# mcu_peripheral.net
KiCad netlist of a schematic drawn in Altium Designer
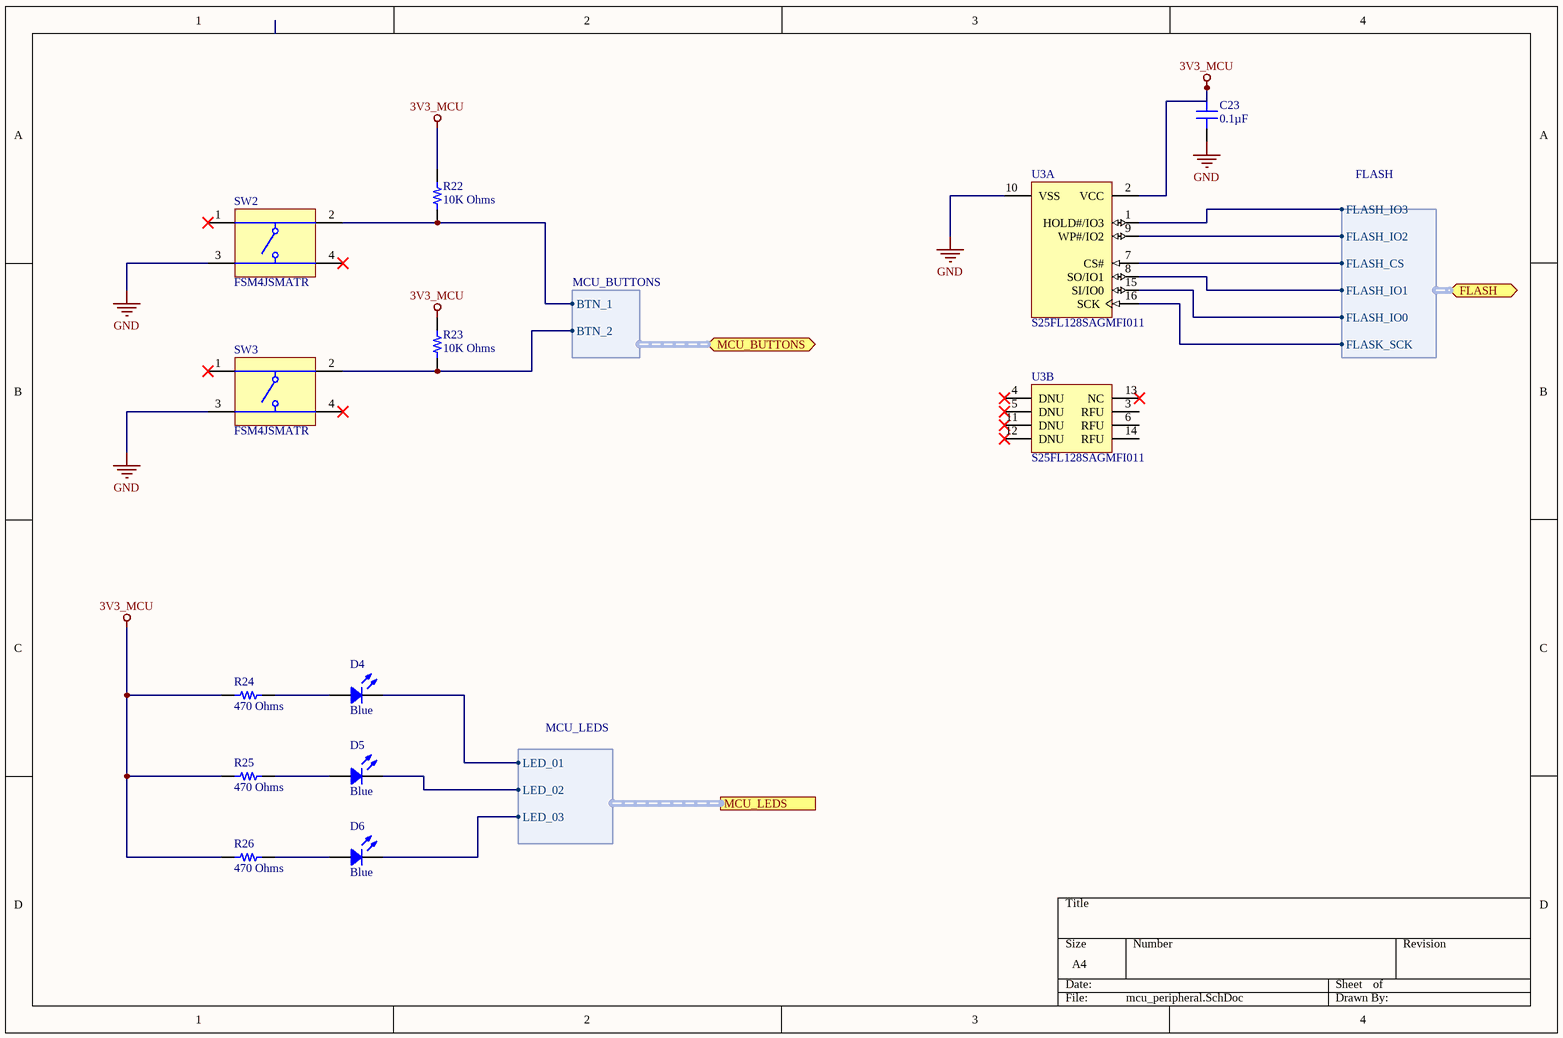
[diagram p0: mcu_peripheral.SchDoc]

(export (version "E")
  (design (tool "Eeschema 10.0.6"))
  (components
    (comp (ref "C23")
      (value "0.1µF")
      (footprint "CAP 0603_1608")
      (description "CAP CER 0.1UF 50V X7R 0603")
      (fields (field (name "PART NUMBER") "C0603C104K5RAC7411") (field (name "MANUFACTURER") "KEMET"))
      (libsource (lib "Celestial Altium Library - altium_library (2)") (part "Capacitor"))
    )
    (comp (ref "D4")
      (value "Blue")
      (footprint "LED 0603_1608 BLUE")
      (description "LED BLUE 0603 SMD")
      (fields
        (field (name "PART NUMBER") "VLMB1300-GS08")
        (field (name "MANUFACTURER") "Vishay Semiconductor Opto Division")
      )
      (libsource (lib "Celestial Altium Library - altium_library (2)") (part "LED"))
    )
    (comp (ref "D5")
      (value "Blue")
      (footprint "LED 0603_1608 BLUE")
      (description "LED BLUE 0603 SMD")
      (fields
        (field (name "PART NUMBER") "VLMB1300-GS08")
        (field (name "MANUFACTURER") "Vishay Semiconductor Opto Division")
      )
      (libsource (lib "Celestial Altium Library - altium_library (2)") (part "LED"))
    )
    (comp (ref "D6")
      (value "Blue")
      (footprint "LED 0603_1608 BLUE")
      (description "LED BLUE 0603 SMD")
      (fields
        (field (name "PART NUMBER") "VLMB1300-GS08")
        (field (name "MANUFACTURER") "Vishay Semiconductor Opto Division")
      )
      (libsource (lib "Celestial Altium Library - altium_library (2)") (part "LED"))
    )
    (comp (ref "R22")
      (value "10K Ohms")
      (footprint "RES 0603_1608")
      (description "RES SMD 470 OHM 5% 1/4W 0603")
      (fields (field (name "PART NUMBER") "CRCW0603470RJNEAHP") (field (name "MANUFACTURER") "Vishay Dale"))
      (libsource (lib "Celestial Altium Library - altium_library (2)") (part "Resistor"))
    )
    (comp (ref "R23")
      (value "10K Ohms")
      (footprint "RES 0603_1608")
      (description "RES SMD 470 OHM 5% 1/4W 0603")
      (fields (field (name "PART NUMBER") "CRCW0603470RJNEAHP") (field (name "MANUFACTURER") "Vishay Dale"))
      (libsource (lib "Celestial Altium Library - altium_library (2)") (part "Resistor"))
    )
    (comp (ref "R24")
      (value "470 Ohms")
      (footprint "RES 0603_1608")
      (description "RES SMD 470 OHM 5% 1/4W 0603")
      (fields (field (name "PART NUMBER") "CRCW0603470RJNEAHP") (field (name "MANUFACTURER") "Vishay Dale"))
      (libsource (lib "Celestial Altium Library - altium_library (2)") (part "Resistor"))
    )
    (comp (ref "R25")
      (value "470 Ohms")
      (footprint "RES 0603_1608")
      (description "RES SMD 470 OHM 5% 1/4W 0603")
      (fields (field (name "PART NUMBER") "CRCW0603470RJNEAHP") (field (name "MANUFACTURER") "Vishay Dale"))
      (libsource (lib "Celestial Altium Library - altium_library (2)") (part "Resistor"))
    )
    (comp (ref "R26")
      (value "470 Ohms")
      (footprint "RES 0603_1608")
      (description "RES SMD 470 OHM 5% 1/4W 0603")
      (fields (field (name "PART NUMBER") "CRCW0603470RJNEAHP") (field (name "MANUFACTURER") "Vishay Dale"))
      (libsource (lib "Celestial Altium Library - altium_library (2)") (part "Resistor"))
    )
    (comp (ref "SW2")
      (value "FSM4JSMATR")
      (footprint "TECO-FSM4JSMATR_V")
      (description "Micro Miniature Push Button Switch FSM JSM, 50 mA, -35 to 85 degC, 4-Pin SMD, RoHS, Tape and Reel")
      (fields (field (name "MANUFACTURER") "TE Connectivity"))
      (libsource (lib "Altium Content Vault") (part "SW-SPST-4_A"))
    )
    (comp (ref "SW3")
      (value "FSM4JSMATR")
      (footprint "TECO-FSM4JSMATR_V")
      (description "Micro Miniature Push Button Switch FSM JSM, 50 mA, -35 to 85 degC, 4-Pin SMD, RoHS, Tape and Reel")
      (fields (field (name "MANUFACTURER") "TE Connectivity"))
      (libsource (lib "Altium Content Vault") (part "SW-SPST-4_A"))
    )
    (comp (ref "U3")
      (value "S25FL128SAGMFI011")
      (footprint "SPSN-SOIC-16_L")
      (fields (field (name "MANUFACTURER") "Spansion"))
      (libsource (lib "") (part "SPSN-S25FL128S-16_1"))
    )
  )
  (nets
    (net (code "4") (name "/BTN_1") (class "Default")
      (node (ref "R22") (pin "1") (pinfunction "1_1") (pintype "passive"))
      (node (ref "SW2") (pin "2") (pinfunction "2_2") (pintype "passive"))
    )
    (net (code "5") (name "/BTN_2") (class "Default")
      (node (ref "R23") (pin "1") (pinfunction "1_1") (pintype "passive"))
      (node (ref "SW3") (pin "2") (pinfunction "2_2") (pintype "passive"))
    )
    (net (code "6") (name "/FLASH_CS") (class "Default")
      (node (ref "U3") (pin "7") (pinfunction "CS#_7") (pintype "input"))
    )
    (net (code "7") (name "/FLASH_IO0") (class "Default")
      (node (ref "U3") (pin "15") (pinfunction "SI/IO0_15") (pintype "bidirectional"))
    )
    (net (code "8") (name "/FLASH_IO1") (class "Default")
      (node (ref "U3") (pin "8") (pinfunction "SO/IO1_8") (pintype "bidirectional"))
    )
    (net (code "9") (name "/FLASH_IO2") (class "Default")
      (node (ref "U3") (pin "9") (pinfunction "WP#/IO2_9") (pintype "bidirectional"))
    )
    (net (code "10") (name "/FLASH_IO3") (class "Default")
      (node (ref "U3") (pin "1") (pinfunction "HOLD#/IO3_1") (pintype "bidirectional"))
    )
    (net (code "11") (name "/FLASK_SCK") (class "Default")
      (node (ref "U3") (pin "16") (pinfunction "SCK_16") (pintype "input"))
    )
    (net (code "12") (name "/LED_01") (class "Default")
      (node (ref "D4") (pin "2") (pinfunction "2_2") (pintype "passive"))
    )
    (net (code "13") (name "/LED_02") (class "Default")
      (node (ref "D5") (pin "2") (pinfunction "2_2") (pintype "passive"))
    )
    (net (code "14") (name "/LED_03") (class "Default")
      (node (ref "D6") (pin "2") (pinfunction "2_2") (pintype "passive"))
    )
    (net (code "18") (name "3V3_MCU") (class "Default")
      (node (ref "C23") (pin "2") (pinfunction "2_2") (pintype "passive"))
      (node (ref "R22") (pin "2") (pinfunction "2_2") (pintype "passive"))
      (node (ref "R23") (pin "2") (pinfunction "2_2") (pintype "passive"))
      (node (ref "R24") (pin "1") (pinfunction "1_1") (pintype "passive"))
      (node (ref "R25") (pin "1") (pinfunction "1_1") (pintype "passive"))
      (node (ref "R26") (pin "1") (pinfunction "1_1") (pintype "passive"))
      (node (ref "U3") (pin "2") (pinfunction "VCC_2") (pintype "power_in"))
    )
    (net (code "19") (name "GND") (class "Default")
      (node (ref "C23") (pin "1") (pinfunction "1_1") (pintype "passive"))
      (node (ref "SW2") (pin "3") (pinfunction "3_3") (pintype "passive"))
      (node (ref "SW3") (pin "3") (pinfunction "3_3") (pintype "passive"))
      (node (ref "U3") (pin "10") (pinfunction "VSS_10") (pintype "power_in"))
    )
    (net (code "20") (name "Net-(D4-Pad1)") (class "Default")
      (node (ref "D4") (pin "1") (pinfunction "1_1") (pintype "passive"))
      (node (ref "R24") (pin "2") (pinfunction "2_2") (pintype "passive"))
    )
    (net (code "21") (name "Net-(D5-Pad1)") (class "Default")
      (node (ref "D5") (pin "1") (pinfunction "1_1") (pintype "passive"))
      (node (ref "R25") (pin "2") (pinfunction "2_2") (pintype "passive"))
    )
    (net (code "22") (name "Net-(D6-Pad1)") (class "Default")
      (node (ref "D6") (pin "1") (pinfunction "1_1") (pintype "passive"))
      (node (ref "R26") (pin "2") (pinfunction "2_2") (pintype "passive"))
    )
    (net (code "23") (name "unconnected-(SW2-Pad1)") (class "Default")
      (node (ref "SW2") (pin "1") (pinfunction "1_1") (pintype "passive+no_connect"))
    )
    (net (code "24") (name "unconnected-(SW2-Pad4)") (class "Default")
      (node (ref "SW2") (pin "4") (pinfunction "4_4") (pintype "passive+no_connect"))
    )
    (net (code "25") (name "unconnected-(SW3-Pad1)") (class "Default")
      (node (ref "SW3") (pin "1") (pinfunction "1_1") (pintype "passive+no_connect"))
    )
    (net (code "26") (name "unconnected-(SW3-Pad4)") (class "Default")
      (node (ref "SW3") (pin "4") (pinfunction "4_4") (pintype "passive+no_connect"))
    )
    (net (code "27") (name "unconnected-(U3B-DNU-Pad4)") (class "Default")
      (node (ref "U3") (pin "4") (pinfunction "DNU_4") (pintype "passive+no_connect"))
    )
    (net (code "28") (name "unconnected-(U3B-DNU-Pad5)") (class "Default")
      (node (ref "U3") (pin "5") (pinfunction "DNU_5") (pintype "passive+no_connect"))
    )
    (net (code "29") (name "unconnected-(U3B-DNU-Pad11)") (class "Default")
      (node (ref "U3") (pin "11") (pinfunction "DNU_11") (pintype "passive+no_connect"))
    )
    (net (code "30") (name "unconnected-(U3B-DNU-Pad12)") (class "Default")
      (node (ref "U3") (pin "12") (pinfunction "DNU_12") (pintype "passive+no_connect"))
    )
    (net (code "31") (name "unconnected-(U3B-NC-Pad13)") (class "Default")
      (node (ref "U3") (pin "13") (pinfunction "NC_13") (pintype "passive+no_connect"))
    )
    (net (code "32") (name "unconnected-(U3B-RFU-Pad3)") (class "Default")
      (node (ref "U3") (pin "3") (pinfunction "RFU_3") (pintype "passive"))
    )
    (net (code "33") (name "unconnected-(U3B-RFU-Pad6)") (class "Default")
      (node (ref "U3") (pin "6") (pinfunction "RFU_6") (pintype "passive"))
    )
    (net (code "34") (name "unconnected-(U3B-RFU-Pad14)") (class "Default")
      (node (ref "U3") (pin "14") (pinfunction "RFU_14") (pintype "passive"))
    )
  )
)
